# Sensor.net
KiCad netlist of a schematic drawn in Altium Designer
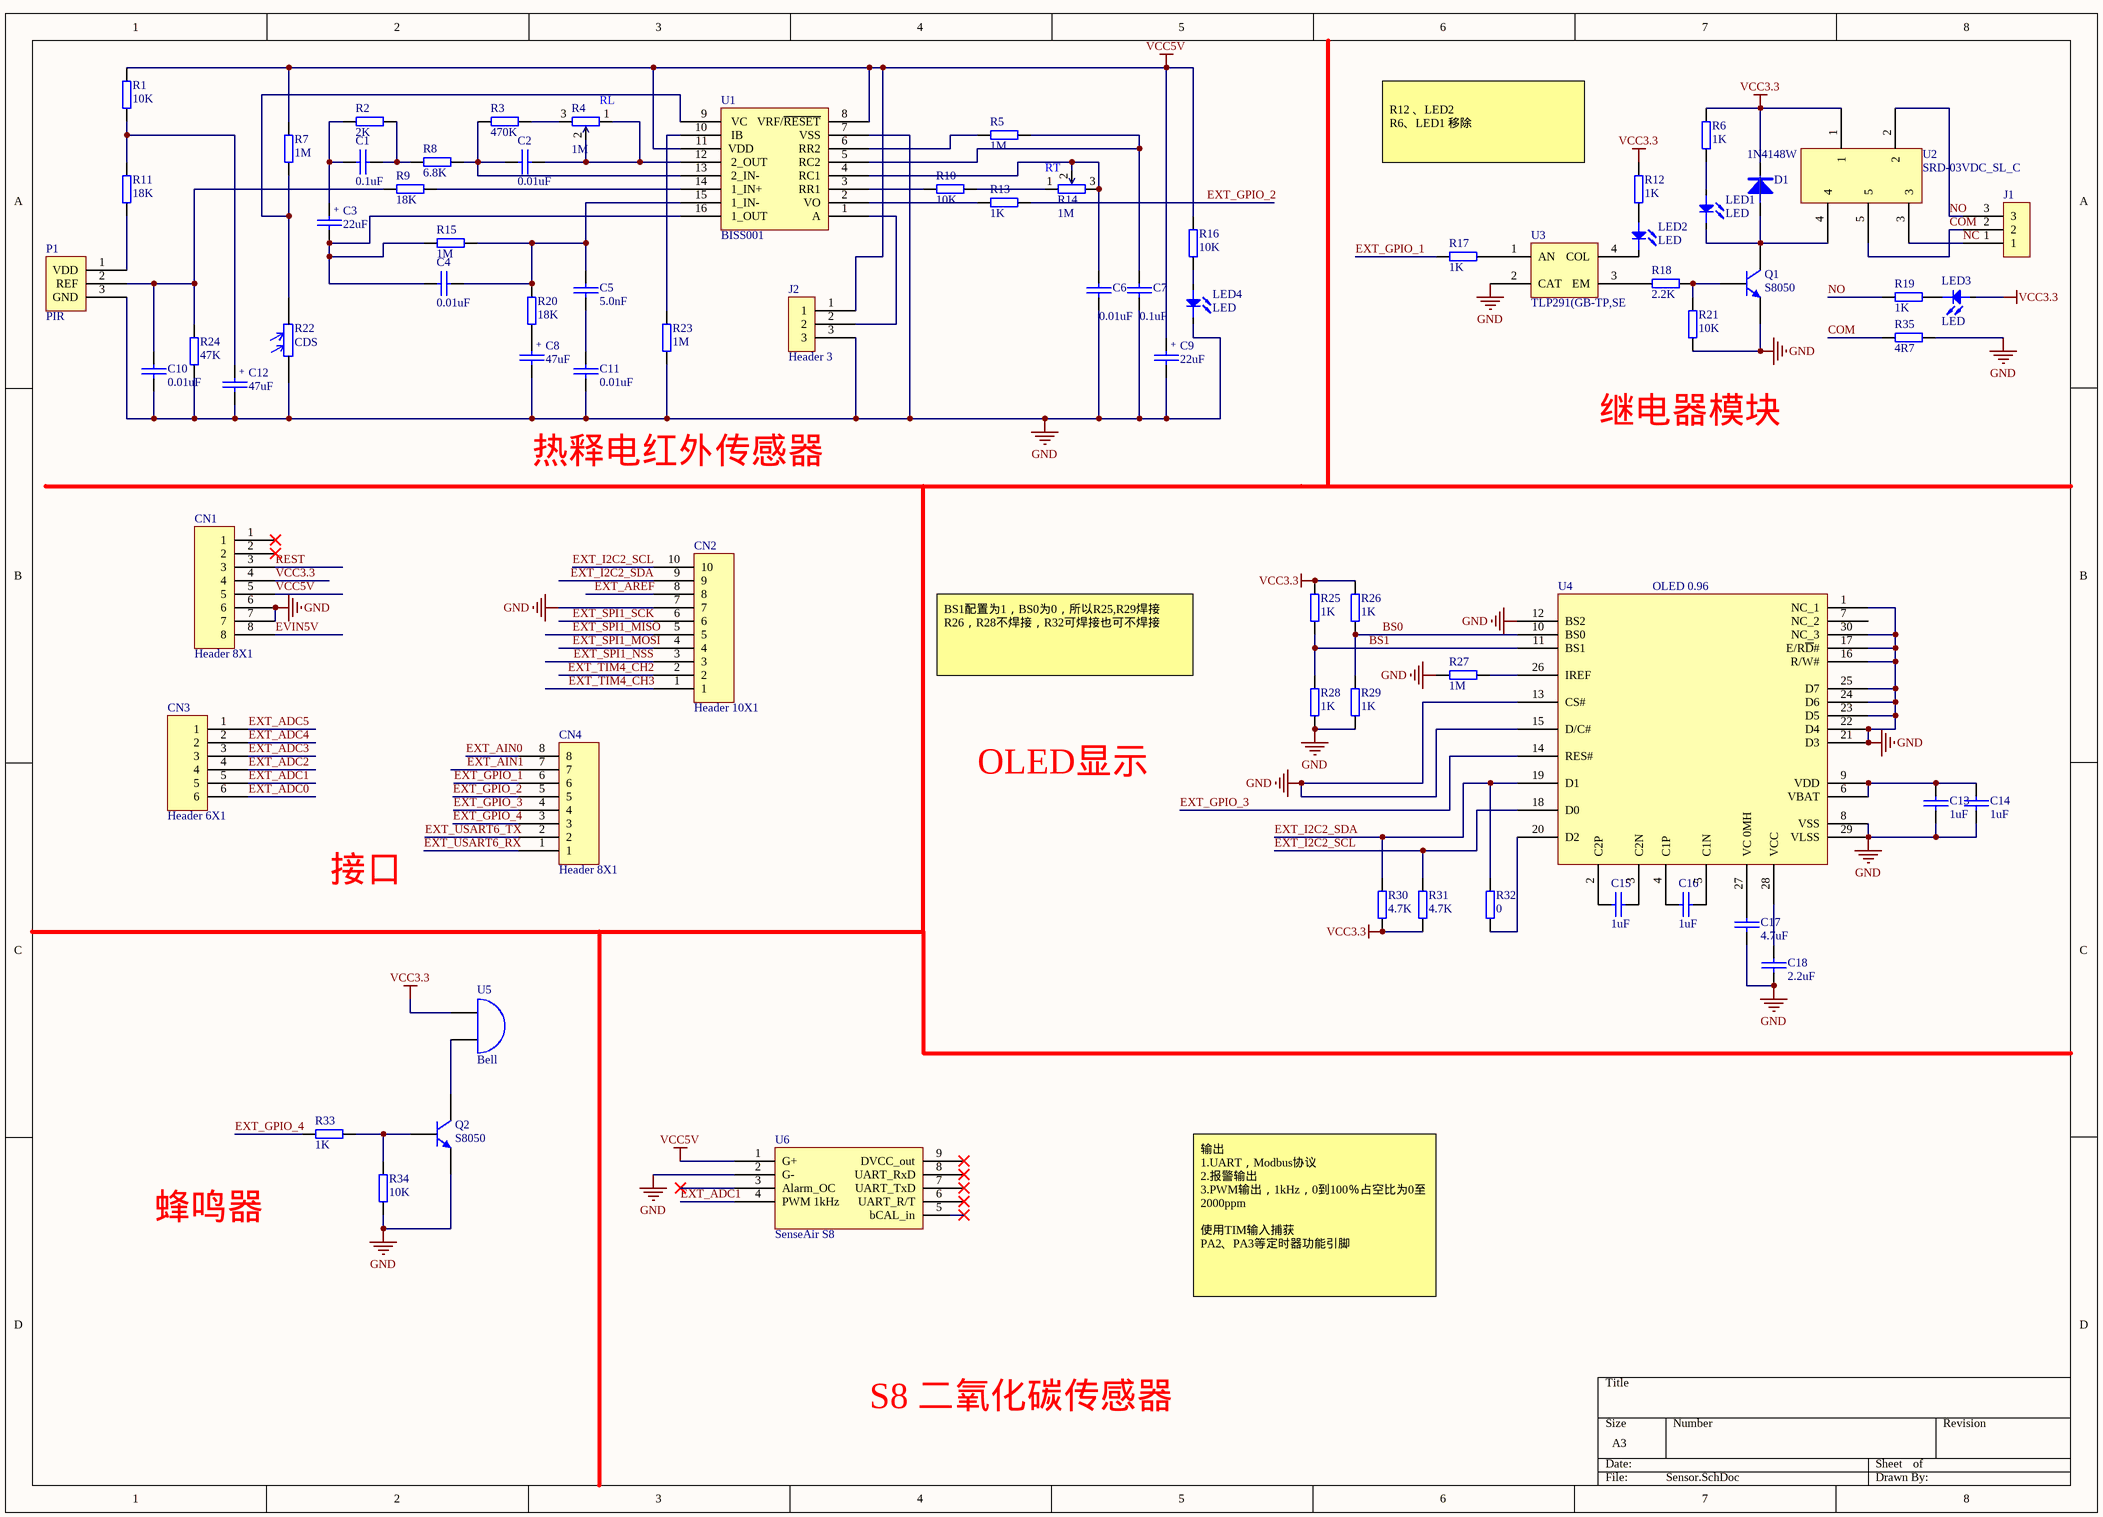
[diagram p0: Sensor.SchDoc]

(export (version "E")
  (design (tool "Eeschema 10.0.6"))
  (components
    (comp (ref "C1")
      (value "0.1uF")
      (footprint "0603 - CAP")
      (libsource (lib "practice") (part "Capacity_normal"))
    )
    (comp (ref "C2")
      (value "0.01uF")
      (footprint "0603 - CAP")
      (libsource (lib "practice") (part "Capacity_normal"))
    )
    (comp (ref "C3")
      (value "22uF")
      (footprint "C-钽贴A(S)_3216M_18(12)")
      (libsource (lib "practice") (part "Capacity_electric"))
    )
    (comp (ref "C4")
      (value "0.01uF")
      (footprint "0603 - CAP")
      (libsource (lib "practice") (part "Capacity_normal"))
    )
    (comp (ref "C5")
      (value "5.0nF")
      (footprint "0603 - CAP")
      (libsource (lib "practice") (part "Capacity_normal"))
    )
    (comp (ref "C6")
      (value "0.01uF")
      (footprint "0603 - CAP")
      (libsource (lib "practice") (part "Capacity_normal"))
    )
    (comp (ref "C7")
      (value "0.1uF")
      (footprint "0603 - CAP")
      (libsource (lib "practice") (part "Capacity_normal"))
    )
    (comp (ref "C8")
      (value "47uF")
      (footprint "C-钽贴A(S)_3216M_18(12)")
      (libsource (lib "practice") (part "Capacity_electric"))
    )
    (comp (ref "C9")
      (value "22uF")
      (footprint "C-钽贴A(S)_3216M_18(12)")
      (libsource (lib "practice") (part "Capacity_electric"))
    )
    (comp (ref "C10")
      (value "0.01uF")
      (footprint "0603 - CAP")
      (libsource (lib "practice") (part "Capacity_normal"))
    )
    (comp (ref "C11")
      (value "0.01uF")
      (footprint "0603 - CAP")
      (libsource (lib "practice") (part "Capacity_normal"))
    )
    (comp (ref "C12")
      (value "47uF")
      (footprint "C-钽贴A(S)_3216M_18(12)")
      (libsource (lib "practice") (part "Capacity_electric"))
    )
    (comp (ref "C13")
      (value "1uF")
      (footprint "0603 - CAP")
      (libsource (lib "practice") (part "Capacity_normal"))
    )
    (comp (ref "C14")
      (value "1uF")
      (footprint "0603 - CAP")
      (libsource (lib "practice") (part "Capacity_normal"))
    )
    (comp (ref "C15")
      (value "1uF")
      (footprint "0603 - CAP")
      (libsource (lib "practice") (part "Capacity_normal"))
    )
    (comp (ref "C16")
      (value "1uF")
      (footprint "0603 - CAP")
      (libsource (lib "practice") (part "Capacity_normal"))
    )
    (comp (ref "C17")
      (value "4.7uF")
      (footprint "0603 - CAP")
      (libsource (lib "practice") (part "Capacity_normal"))
    )
    (comp (ref "C18")
      (value "2.2uF")
      (footprint "0603 - CAP")
      (libsource (lib "practice") (part "Capacity_normal"))
    )
    (comp (ref "CN1") (value "Header 8X1") (footprint "HDR1X8") (libsource (lib "") (part "Header 8X1_1")))
    (comp (ref "CN2")
      (value "Header 10X1")
      (footprint "HDR1X10")
      (libsource (lib "practice") (part "Header 10X1"))
    )
    (comp (ref "CN3")
      (value "Header 6X1")
      (footprint "HDR1X6")
      (libsource (lib "practice") (part "Header 6X1"))
    )
    (comp (ref "CN4")
      (value "Header 8X1")
      (footprint "HDR1X8")
      (libsource (lib "practice") (part "Header 8X1"))
    )
    (comp (ref "D1") (value "1N4148W") (footprint "1N4148W") (libsource (lib "practice") (part "1N4148W")))
    (comp (ref "J1")
      (value "~")
      (footprint "HDR1X3 - duplicate1")
      (description "Header,3-pin")
      (libsource (lib "practice") (part "Header 3"))
    )
    (comp (ref "J2")
      (value "Header 3")
      (footprint "HDR1X3 - duplicate1")
      (description "Header,3-pin")
      (libsource (lib "") (part "Header 3_1"))
    )
    (comp (ref "LED1") (value "LED") (footprint "0603-LED") (libsource (lib "practice") (part "LED")))
    (comp (ref "LED2") (value "LED") (footprint "0603-LED") (libsource (lib "practice") (part "LED")))
    (comp (ref "LED3") (value "LED") (footprint "0603-LED") (libsource (lib "practice") (part "LED")))
    (comp (ref "LED4") (value "LED") (footprint "0603-LED") (libsource (lib "practice") (part "LED")))
    (comp (ref "P1") (value "PIR") (footprint "PIR") (libsource (lib "practice") (part "PIR")))
    (comp (ref "Q1") (value "S8050") (footprint "TO-92_3") (libsource (lib "practice") (part "S8050")))
    (comp (ref "Q2") (value "S8050") (footprint "TO-92_3") (libsource (lib "practice") (part "S8050")))
    (comp (ref "R1") (value "10K") (footprint "0603 - RES") (libsource (lib "practice") (part "RES")))
    (comp (ref "R2") (value "2K") (footprint "0603 - RES") (libsource (lib "practice") (part "RES")))
    (comp (ref "R3") (value "470K") (footprint "0603 - RES") (libsource (lib "practice") (part "RES")))
    (comp (ref "R4") (value "1M") (footprint "3296W") (libsource (lib "practice") (part "可调电阻")))
    (comp (ref "R5") (value "1M") (footprint "0603 - RES") (libsource (lib "practice") (part "RES")))
    (comp (ref "R6") (value "1K") (footprint "0603 - RES") (libsource (lib "practice") (part "RES")))
    (comp (ref "R7") (value "1M") (footprint "0603 - RES") (libsource (lib "practice") (part "RES")))
    (comp (ref "R8") (value "6.8K") (footprint "0603 - RES") (libsource (lib "practice") (part "RES")))
    (comp (ref "R9") (value "18K") (footprint "0603 - RES") (libsource (lib "practice") (part "RES")))
    (comp (ref "R10") (value "10K") (footprint "0603 - RES") (libsource (lib "practice") (part "RES")))
    (comp (ref "R11") (value "18K") (footprint "0603 - RES") (libsource (lib "practice") (part "RES")))
    (comp (ref "R12") (value "1K") (footprint "0603 - RES") (libsource (lib "practice") (part "RES")))
    (comp (ref "R13") (value "1K") (footprint "0603 - RES") (libsource (lib "practice") (part "RES")))
    (comp (ref "R14") (value "1M") (footprint "3296W") (libsource (lib "practice") (part "可调电阻")))
    (comp (ref "R15") (value "1M") (footprint "0603 - RES") (libsource (lib "practice") (part "RES")))
    (comp (ref "R16") (value "10K") (footprint "0603 - RES") (libsource (lib "practice") (part "RES")))
    (comp (ref "R17") (value "1K") (footprint "0603 - RES") (libsource (lib "practice") (part "RES")))
    (comp (ref "R18") (value "2.2K") (footprint "0603 - RES") (libsource (lib "practice") (part "RES")))
    (comp (ref "R19") (value "1K") (footprint "0603 - RES") (libsource (lib "practice") (part "RES")))
    (comp (ref "R20") (value "18K") (footprint "0603 - RES") (libsource (lib "practice") (part "RES")))
    (comp (ref "R21") (value "10K") (footprint "0603 - RES") (libsource (lib "practice") (part "RES")))
    (comp (ref "R22") (value "CDS") (footprint "RES-guangmin") (libsource (lib "practice") (part "光敏电阻")))
    (comp (ref "R23") (value "1M") (footprint "0603 - RES") (libsource (lib "practice") (part "RES")))
    (comp (ref "R24") (value "47K") (footprint "0603 - RES") (libsource (lib "practice") (part "RES")))
    (comp (ref "R25") (value "1K") (footprint "0603 - RES") (libsource (lib "practice") (part "RES")))
    (comp (ref "R26") (value "1K") (footprint "0603 - RES") (libsource (lib "practice") (part "RES")))
    (comp (ref "R27") (value "1M") (footprint "0603 - RES") (libsource (lib "practice") (part "RES")))
    (comp (ref "R28") (value "1K") (footprint "0603 - RES") (libsource (lib "practice") (part "RES")))
    (comp (ref "R29") (value "1K") (footprint "0603 - RES") (libsource (lib "practice") (part "RES")))
    (comp (ref "R30") (value "4.7K") (footprint "0603 - RES") (libsource (lib "practice") (part "RES")))
    (comp (ref "R31") (value "4.7K") (footprint "0603 - RES") (libsource (lib "practice") (part "RES")))
    (comp (ref "R32") (value "0") (footprint "0603 - RES") (libsource (lib "电阻") (part "RES")))
    (comp (ref "R33") (value "1K") (footprint "0603 - RES") (libsource (lib "practice") (part "RES")))
    (comp (ref "R34") (value "10K") (footprint "0603 - RES") (libsource (lib "practice") (part "RES")))
    (comp (ref "R35") (value "4R7") (footprint "0603 - RES") (libsource (lib "practice") (part "RES")))
    (comp (ref "U1")
      (value "BISS001")
      (footprint "SOP-16_150mil")
      (description "热释电传感器")
      (libsource (lib "practice") (part "BISS001"))
    )
    (comp (ref "U2")
      (value "SRD-03VDC_SL_C")
      (footprint "SRD-03VDC-SL-C")
      (description "SL，3V 继电器模块")
      (libsource (lib "practice") (part "SRD-03VDC_SL_C"))
    )
    (comp (ref "U3")
      (value "TLP291(GB-TP,SE")
      (footprint "TLP291(GB-TP,SE")
      (libsource (lib "practice") (part "TLP291(GB-TP,SE"))
    )
    (comp (ref "U4")
      (value "OLED 0.96")
      (footprint "oled 0.96")
      (description "中景园 0.96寸OLED 30pin")
      (libsource (lib "practice") (part "OLED 0.96"))
    )
    (comp (ref "U5") (value "Bell") (footprint "BUZZER_mini") (libsource (lib "practice") (part "Bell")))
    (comp (ref "U6")
      (value "SenseAir S8")
      (footprint "SenseAir S8")
      (libsource (lib "practice") (part "SenseAir S8"))
    )
  )
  (nets
    (net (code "1") (name "/BS0") (class "Default")
      (node (ref "R26") (pin "1") (pinfunction "1_1") (pintype "passive"))
      (node (ref "R29") (pin "2") (pinfunction "2_2") (pintype "passive"))
      (node (ref "U4") (pin "10") (pinfunction "BS0_10") (pintype "passive"))
    )
    (net (code "2") (name "/BS1") (class "Default")
      (node (ref "R25") (pin "1") (pinfunction "1_1") (pintype "passive"))
      (node (ref "R28") (pin "2") (pinfunction "2_2") (pintype "passive"))
      (node (ref "U4") (pin "11") (pinfunction "BS1_11") (pintype "passive"))
    )
    (net (code "3") (name "/COM") (class "Default")
      (node (ref "J1") (pin "2") (pinfunction "2_2") (pintype "passive"))
      (node (ref "R35") (pin "1") (pinfunction "1_1") (pintype "passive"))
      (node (ref "U2") (pin "5") (pinfunction "5_5") (pintype "passive"))
    )
    (net (code "4") (name "/EVIN5V") (class "Default")
      (node (ref "CN1") (pin "8") (pinfunction "8_8") (pintype "passive"))
    )
    (net (code "5") (name "/EXT_ADC0") (class "Default")
      (node (ref "CN3") (pin "6") (pinfunction "6_6") (pintype "passive"))
    )
    (net (code "6") (name "/EXT_ADC1") (class "Default")
      (node (ref "CN3") (pin "5") (pinfunction "5_5") (pintype "passive"))
      (node (ref "U6") (pin "4") (pinfunction "PWM_1kHz_4") (pintype "passive"))
    )
    (net (code "7") (name "/EXT_ADC2") (class "Default")
      (node (ref "CN3") (pin "4") (pinfunction "4_4") (pintype "passive"))
    )
    (net (code "8") (name "/EXT_ADC3") (class "Default")
      (node (ref "CN3") (pin "3") (pinfunction "3_3") (pintype "passive"))
    )
    (net (code "9") (name "/EXT_ADC4") (class "Default")
      (node (ref "CN3") (pin "2") (pinfunction "2_2") (pintype "passive"))
    )
    (net (code "10") (name "/EXT_ADC5") (class "Default")
      (node (ref "CN3") (pin "1") (pinfunction "1_1") (pintype "passive"))
    )
    (net (code "11") (name "/EXT_AIN0") (class "Default")
      (node (ref "CN4") (pin "8") (pinfunction "8_8") (pintype "passive"))
    )
    (net (code "12") (name "/EXT_AIN1") (class "Default")
      (node (ref "CN4") (pin "7") (pinfunction "7_7") (pintype "passive"))
    )
    (net (code "13") (name "/EXT_AREF") (class "Default")
      (node (ref "CN2") (pin "8") (pinfunction "8_8") (pintype "passive"))
    )
    (net (code "14") (name "/EXT_GPIO_1") (class "Default")
      (node (ref "CN4") (pin "6") (pinfunction "6_6") (pintype "passive"))
      (node (ref "R17") (pin "1") (pinfunction "1_1") (pintype "passive"))
    )
    (net (code "15") (name "/EXT_GPIO_2") (class "Default")
      (node (ref "CN4") (pin "5") (pinfunction "5_5") (pintype "passive"))
      (node (ref "R13") (pin "2") (pinfunction "2_2") (pintype "passive"))
    )
    (net (code "16") (name "/EXT_GPIO_3") (class "Default")
      (node (ref "CN4") (pin "4") (pinfunction "4_4") (pintype "passive"))
      (node (ref "U4") (pin "14") (pinfunction "RES#_14") (pintype "passive"))
    )
    (net (code "17") (name "/EXT_GPIO_4") (class "Default")
      (node (ref "CN4") (pin "3") (pinfunction "3_3") (pintype "passive"))
      (node (ref "R33") (pin "1") (pinfunction "1_1") (pintype "passive"))
    )
    (net (code "18") (name "/EXT_I2C2_SCL") (class "Default")
      (node (ref "CN2") (pin "10") (pinfunction "10_10") (pintype "passive"))
      (node (ref "R31") (pin "2") (pinfunction "2_2") (pintype "passive"))
      (node (ref "U4") (pin "18") (pinfunction "D0_18") (pintype "passive"))
    )
    (net (code "19") (name "/EXT_I2C2_SDA") (class "Default")
      (node (ref "CN2") (pin "9") (pinfunction "9_9") (pintype "passive"))
      (node (ref "R30") (pin "2") (pinfunction "2_2") (pintype "passive"))
      (node (ref "R32") (pin "2") (pinfunction "2_2") (pintype "passive"))
      (node (ref "U4") (pin "19") (pinfunction "D1_19") (pintype "passive"))
    )
    (net (code "20") (name "/EXT_SPI1_MISO") (class "Default")
      (node (ref "CN2") (pin "5") (pinfunction "5_5") (pintype "passive"))
    )
    (net (code "21") (name "/EXT_SPI1_MOSI") (class "Default")
      (node (ref "CN2") (pin "4") (pinfunction "4_4") (pintype "passive"))
    )
    (net (code "22") (name "/EXT_SPI1_NSS") (class "Default")
      (node (ref "CN2") (pin "3") (pinfunction "3_3") (pintype "passive"))
    )
    (net (code "23") (name "/EXT_SPI1_SCK") (class "Default")
      (node (ref "CN2") (pin "6") (pinfunction "6_6") (pintype "passive"))
    )
    (net (code "24") (name "/EXT_TIM4_CH2") (class "Default")
      (node (ref "CN2") (pin "2") (pinfunction "2_2") (pintype "passive"))
    )
    (net (code "25") (name "/EXT_TIM4_CH3") (class "Default")
      (node (ref "CN2") (pin "1") (pinfunction "1_1") (pintype "passive"))
    )
    (net (code "26") (name "/EXT_USART6_RX") (class "Default")
      (node (ref "CN4") (pin "1") (pinfunction "1_1") (pintype "passive"))
    )
    (net (code "27") (name "/EXT_USART6_TX") (class "Default")
      (node (ref "CN4") (pin "2") (pinfunction "2_2") (pintype "passive"))
    )
    (net (code "28") (name "/NC") (class "Default")
      (node (ref "J1") (pin "1") (pinfunction "1_1") (pintype "passive"))
      (node (ref "U2") (pin "3") (pinfunction "3_3") (pintype "passive"))
    )
    (net (code "29") (name "/NO") (class "Default")
      (node (ref "J1") (pin "3") (pinfunction "3_3") (pintype "passive"))
      (node (ref "R19") (pin "1") (pinfunction "1_1") (pintype "passive"))
      (node (ref "U2") (pin "2") (pinfunction "2_2") (pintype "passive"))
    )
    (net (code "30") (name "/REST") (class "Default")
      (node (ref "CN1") (pin "3") (pinfunction "3_3") (pintype "passive"))
    )
    (net (code "31") (name "GND") (class "Default")
      (node (ref "C10") (pin "2") (pinfunction "2_2") (pintype "passive"))
      (node (ref "C11") (pin "2") (pinfunction "2_2") (pintype "passive"))
      (node (ref "C12") (pin "2") (pinfunction "2_2") (pintype "passive"))
      (node (ref "C13") (pin "1") (pinfunction "1_1") (pintype "passive"))
      (node (ref "C14") (pin "1") (pinfunction "1_1") (pintype "passive"))
      (node (ref "C17") (pin "1") (pinfunction "1_1") (pintype "passive"))
      (node (ref "C18") (pin "1") (pinfunction "1_1") (pintype "passive"))
      (node (ref "C6") (pin "2") (pinfunction "2_2") (pintype "passive"))
      (node (ref "C7") (pin "2") (pinfunction "2_2") (pintype "passive"))
      (node (ref "C8") (pin "2") (pinfunction "2_2") (pintype "passive"))
      (node (ref "C9") (pin "2") (pinfunction "2_2") (pintype "passive"))
      (node (ref "CN1") (pin "6") (pinfunction "6_6") (pintype "passive"))
      (node (ref "CN1") (pin "7") (pinfunction "7_7") (pintype "passive"))
      (node (ref "CN2") (pin "7") (pinfunction "7_7") (pintype "passive"))
      (node (ref "J2") (pin "3") (pinfunction "3_3") (pintype "passive"))
      (node (ref "LED4") (pin "2") (pintype "passive"))
      (node (ref "P1") (pin "3") (pinfunction "GND_3") (pintype "passive"))
      (node (ref "Q1") (pin "1") (pinfunction "E_1") (pintype "passive"))
      (node (ref "Q2") (pin "1") (pinfunction "E_1") (pintype "passive"))
      (node (ref "R21") (pin "2") (pinfunction "2_2") (pintype "passive"))
      (node (ref "R22") (pin "1") (pinfunction "1_1") (pintype "passive"))
      (node (ref "R23") (pin "1") (pinfunction "1_1") (pintype "passive"))
      (node (ref "R24") (pin "1") (pinfunction "1_1") (pintype "passive"))
      (node (ref "R27") (pin "2") (pinfunction "2_2") (pintype "passive"))
      (node (ref "R28") (pin "1") (pinfunction "1_1") (pintype "passive"))
      (node (ref "R29") (pin "1") (pinfunction "1_1") (pintype "passive"))
      (node (ref "R34") (pin "1") (pinfunction "1_1") (pintype "passive"))
      (node (ref "R35") (pin "2") (pinfunction "2_2") (pintype "passive"))
      (node (ref "U1") (pin "7") (pinfunction "VSS_7") (pintype "passive"))
      (node (ref "U3") (pin "2") (pinfunction "CAT_2") (pintype "passive"))
      (node (ref "U4") (pin "1") (pinfunction "NC_1_1") (pintype "passive"))
      (node (ref "U4") (pin "12") (pinfunction "BS2_12") (pintype "passive"))
      (node (ref "U4") (pin "13") (pinfunction "CS#_13") (pintype "passive"))
      (node (ref "U4") (pin "15") (pinfunction "D/C#_15") (pintype "passive"))
      (node (ref "U4") (pin "16") (pinfunction "R/W#_16") (pintype "passive"))
      (node (ref "U4") (pin "17") (pinfunction "E/R~{D}#_17") (pintype "passive"))
      (node (ref "U4") (pin "21") (pinfunction "D3_21") (pintype "passive"))
      (node (ref "U4") (pin "22") (pinfunction "D4_22") (pintype "passive"))
      (node (ref "U4") (pin "23") (pinfunction "D5_23") (pintype "passive"))
      (node (ref "U4") (pin "24") (pinfunction "D6_24") (pintype "passive"))
      (node (ref "U4") (pin "25") (pinfunction "D7_25") (pintype "passive"))
      (node (ref "U4") (pin "29") (pinfunction "VLSS_29") (pintype "passive"))
      (node (ref "U4") (pin "30") (pinfunction "NC_3_30") (pintype "passive"))
      (node (ref "U4") (pin "8") (pinfunction "VSS_8") (pintype "passive"))
      (node (ref "U6") (pin "2") (pinfunction "G-_2") (pintype "passive"))
    )
    (net (code "32") (name "Net-(C1-Pad1)") (class "Default")
      (node (ref "C1") (pin "1") (pinfunction "1_1") (pintype "passive"))
      (node (ref "R2") (pin "2") (pinfunction "2_2") (pintype "passive"))
      (node (ref "R8") (pin "1") (pinfunction "1_1") (pintype "passive"))
    )
    (net (code "33") (name "Net-(C1-Pad2)") (class "Default")
      (node (ref "C1") (pin "2") (pinfunction "2_2") (pintype "passive"))
      (node (ref "C3") (pin "1") (pinfunction "1_1") (pintype "passive"))
      (node (ref "R2") (pin "1") (pinfunction "1_1") (pintype "passive"))
    )
    (net (code "34") (name "Net-(C8-Pad1)") (class "Default")
      (node (ref "C8") (pin "1") (pinfunction "1_1") (pintype "passive"))
      (node (ref "R20") (pin "1") (pinfunction "1_1") (pintype "passive"))
    )
    (net (code "35") (name "Net-(C11-Pad1)") (class "Default")
      (node (ref "C11") (pin "1") (pinfunction "1_1") (pintype "passive"))
      (node (ref "C5") (pin "2") (pinfunction "2_2") (pintype "passive"))
    )
    (net (code "36") (name "Net-(C12-Pad1)") (class "Default")
      (node (ref "C12") (pin "1") (pinfunction "1_1") (pintype "passive"))
      (node (ref "R1") (pin "1") (pinfunction "1_1") (pintype "passive"))
      (node (ref "R11") (pin "2") (pinfunction "2_2") (pintype "passive"))
    )
    (net (code "37") (name "Net-(D1-A)") (class "Default")
      (node (ref "D1") (pin "1") (pinfunction "A_1") (pintype "passive"))
      (node (ref "LED1") (pin "2") (pintype "passive"))
      (node (ref "Q1") (pin "3") (pinfunction "C_3") (pintype "passive"))
      (node (ref "U2") (pin "4") (pinfunction "4_4") (pintype "passive"))
    )
    (net (code "38") (name "Net-(LED1-Pad1)") (class "Default")
      (node (ref "LED1") (pin "1") (pintype "passive"))
      (node (ref "R6") (pin "1") (pinfunction "1_1") (pintype "passive"))
    )
    (net (code "39") (name "Net-(LED2-Pad1)") (class "Default")
      (node (ref "LED2") (pin "1") (pintype "passive"))
      (node (ref "R12") (pin "1") (pinfunction "1_1") (pintype "passive"))
    )
    (net (code "40") (name "Net-(LED3-Pad2)") (class "Default")
      (node (ref "LED3") (pin "2") (pintype "passive"))
      (node (ref "R19") (pin "2") (pinfunction "2_2") (pintype "passive"))
    )
    (net (code "41") (name "Net-(LED4-Pad1)") (class "Default")
      (node (ref "LED4") (pin "1") (pintype "passive"))
      (node (ref "R16") (pin "1") (pinfunction "1_1") (pintype "passive"))
    )
    (net (code "42") (name "Net-(P1-REF)") (class "Default")
      (node (ref "C10") (pin "1") (pinfunction "1_1") (pintype "passive"))
      (node (ref "P1") (pin "2") (pinfunction "REF_2") (pintype "passive"))
      (node (ref "R24") (pin "2") (pinfunction "2_2") (pintype "passive"))
      (node (ref "R9") (pin "2") (pinfunction "2_2") (pintype "passive"))
    )
    (net (code "43") (name "Net-(P1-VDD)") (class "Default")
      (node (ref "P1") (pin "1") (pinfunction "VDD_1") (pintype "passive"))
      (node (ref "R11") (pin "1") (pinfunction "1_1") (pintype "passive"))
    )
    (net (code "44") (name "Net-(Q1-B)") (class "Default")
      (node (ref "Q1") (pin "2") (pinfunction "B_2") (pintype "passive"))
      (node (ref "R18") (pin "1") (pinfunction "1_1") (pintype "passive"))
      (node (ref "R21") (pin "1") (pinfunction "1_1") (pintype "passive"))
    )
    (net (code "45") (name "Net-(Q2-B)") (class "Default")
      (node (ref "Q2") (pin "2") (pinfunction "B_2") (pintype "passive"))
      (node (ref "R33") (pin "2") (pinfunction "2_2") (pintype "passive"))
      (node (ref "R34") (pin "2") (pinfunction "2_2") (pintype "passive"))
    )
    (net (code "46") (name "Net-(Q2-C)") (class "Default")
      (node (ref "Q2") (pin "3") (pinfunction "C_3") (pintype "passive"))
      (node (ref "U5") (pin "2") (pinfunction "B_2") (pintype "passive"))
    )
    (net (code "47") (name "Net-(R3-Pad2)") (class "Default")
      (node (ref "R3") (pin "2") (pinfunction "2_2") (pintype "passive"))
      (node (ref "R4") (pin "3") (pinfunction "3_3") (pintype "passive"))
    )
    (net (code "48") (name "Net-(R10-Pad1)") (class "Default")
      (node (ref "R10") (pin "1") (pinfunction "1_1") (pintype "passive"))
      (node (ref "R14") (pin "1") (pinfunction "1_1") (pintype "passive"))
    )
    (net (code "49") (name "Net-(U1-A)") (class "Default")
      (node (ref "J2") (pin "2") (pinfunction "2_2") (pintype "passive"))
      (node (ref "U1") (pin "1") (pinfunction "A_1") (pintype "passive"))
    )
    (net (code "50") (name "Net-(U1-RC1)") (class "Default")
      (node (ref "C6") (pin "1") (pinfunction "1_1") (pintype "passive"))
      (node (ref "R14") (pin "2") (pinfunction "2_2") (pintype "passive"))
      (node (ref "R14") (pin "3") (pinfunction "3_3") (pintype "passive"))
      (node (ref "U1") (pin "4") (pinfunction "RC1_4") (pintype "passive"))
    )
    (net (code "51") (name "Net-(U1-RC2)") (class "Default")
      (node (ref "C7") (pin "1") (pinfunction "1_1") (pintype "passive"))
      (node (ref "R5") (pin "1") (pinfunction "1_1") (pintype "passive"))
      (node (ref "U1") (pin "5") (pinfunction "RC2_5") (pintype "passive"))
    )
    (net (code "52") (name "Net-(U1-RR1)") (class "Default")
      (node (ref "R10") (pin "2") (pinfunction "2_2") (pintype "passive"))
      (node (ref "U1") (pin "3") (pinfunction "RR1_3") (pintype "passive"))
    )
    (net (code "53") (name "Net-(U1-VO)") (class "Default")
      (node (ref "R13") (pin "1") (pinfunction "1_1") (pintype "passive"))
      (node (ref "U1") (pin "2") (pinfunction "VO_2") (pintype "passive"))
    )
    (net (code "54") (name "Net-(U1-_1_IN+)") (class "Default")
      (node (ref "R9") (pin "1") (pinfunction "1_1") (pintype "passive"))
      (node (ref "U1") (pin "14") (pinfunction "_1_IN+_14") (pintype "passive"))
    )
    (net (code "55") (name "Net-(U1-_1_IN-)") (class "Default")
      (node (ref "C4") (pin "2") (pinfunction "2_2") (pintype "passive"))
      (node (ref "C5") (pin "1") (pinfunction "1_1") (pintype "passive"))
      (node (ref "R15") (pin "1") (pinfunction "1_1") (pintype "passive"))
      (node (ref "R20") (pin "2") (pinfunction "2_2") (pintype "passive"))
      (node (ref "U1") (pin "15") (pinfunction "_1_IN-_15") (pintype "passive"))
    )
    (net (code "56") (name "Net-(U1-_1_OUT)") (class "Default")
      (node (ref "C3") (pin "2") (pinfunction "2_2") (pintype "passive"))
      (node (ref "C4") (pin "1") (pinfunction "1_1") (pintype "passive"))
      (node (ref "R15") (pin "2") (pinfunction "2_2") (pintype "passive"))
      (node (ref "U1") (pin "16") (pinfunction "_1_OUT_16") (pintype "passive"))
    )
    (net (code "57") (name "Net-(U1-_2_IN-)") (class "Default")
      (node (ref "C2") (pin "1") (pinfunction "1_1") (pintype "passive"))
      (node (ref "R3") (pin "1") (pinfunction "1_1") (pintype "passive"))
      (node (ref "R8") (pin "2") (pinfunction "2_2") (pintype "passive"))
      (node (ref "U1") (pin "13") (pinfunction "_2_IN-_13") (pintype "passive"))
    )
    (net (code "58") (name "Net-(U1-_2_OUT)") (class "Default")
      (node (ref "C2") (pin "2") (pinfunction "2_2") (pintype "passive"))
      (node (ref "R4") (pin "1") (pinfunction "1_1") (pintype "passive"))
      (node (ref "R4") (pin "2") (pinfunction "2_2") (pintype "passive"))
      (node (ref "U1") (pin "12") (pinfunction "_2_OUT_12") (pintype "passive"))
    )
    (net (code "59") (name "Net-(U1-_IB)") (class "Default")
      (node (ref "R23") (pin "2") (pinfunction "2_2") (pintype "passive"))
      (node (ref "U1") (pin "10") (pinfunction "_IB_10") (pintype "passive"))
    )
    (net (code "60") (name "Net-(U1-_RR2)") (class "Default")
      (node (ref "R5") (pin "2") (pinfunction "2_2") (pintype "passive"))
      (node (ref "U1") (pin "6") (pinfunction "_RR2_6") (pintype "passive"))
    )
    (net (code "61") (name "Net-(U1-_VC)") (class "Default")
      (node (ref "R22") (pin "2") (pinfunction "2_2") (pintype "passive"))
      (node (ref "R7") (pin "1") (pinfunction "1_1") (pintype "passive"))
      (node (ref "U1") (pin "9") (pinfunction "_VC_9") (pintype "passive"))
    )
    (net (code "62") (name "Net-(U3-AN)") (class "Default")
      (node (ref "R17") (pin "2") (pinfunction "2_2") (pintype "passive"))
      (node (ref "U3") (pin "1") (pinfunction "AN_1") (pintype "passive"))
    )
    (net (code "63") (name "Net-(U3-COL)") (class "Default")
      (node (ref "LED2") (pin "2") (pintype "passive"))
      (node (ref "U3") (pin "4") (pinfunction "COL_4") (pintype "passive"))
    )
    (net (code "64") (name "Net-(U3-EM)") (class "Default")
      (node (ref "R18") (pin "2") (pinfunction "2_2") (pintype "passive"))
      (node (ref "U3") (pin "3") (pinfunction "EM_3") (pintype "passive"))
    )
    (net (code "65") (name "Net-(U4-C1N)") (class "Default")
      (node (ref "C16") (pin "1") (pinfunction "1_1") (pintype "passive"))
      (node (ref "U4") (pin "5") (pinfunction "C1N_5") (pintype "passive"))
    )
    (net (code "66") (name "Net-(U4-C1P)") (class "Default")
      (node (ref "C16") (pin "2") (pinfunction "2_2") (pintype "passive"))
      (node (ref "U4") (pin "4") (pinfunction "C1P_4") (pintype "passive"))
    )
    (net (code "67") (name "Net-(U4-C2N)") (class "Default")
      (node (ref "C15") (pin "1") (pinfunction "1_1") (pintype "passive"))
      (node (ref "U4") (pin "3") (pinfunction "C2N_3") (pintype "passive"))
    )
    (net (code "68") (name "Net-(U4-C2P)") (class "Default")
      (node (ref "C15") (pin "2") (pinfunction "2_2") (pintype "passive"))
      (node (ref "U4") (pin "2") (pinfunction "C2P_2") (pintype "passive"))
    )
    (net (code "69") (name "Net-(U4-D2)") (class "Default")
      (node (ref "R32") (pin "1") (pinfunction "1_1") (pintype "passive"))
      (node (ref "U4") (pin "20") (pinfunction "D2_20") (pintype "passive"))
    )
    (net (code "70") (name "Net-(U4-IREF)") (class "Default")
      (node (ref "R27") (pin "1") (pinfunction "1_1") (pintype "passive"))
      (node (ref "U4") (pin "26") (pinfunction "IREF_26") (pintype "passive"))
    )
    (net (code "71") (name "Net-(U4-VBAT)") (class "Default")
      (node (ref "C13") (pin "2") (pinfunction "2_2") (pintype "passive"))
      (node (ref "C14") (pin "2") (pinfunction "2_2") (pintype "passive"))
      (node (ref "U4") (pin "6") (pinfunction "VBAT_6") (pintype "passive"))
      (node (ref "U4") (pin "9") (pinfunction "VDD_9") (pintype "passive"))
    )
    (net (code "72") (name "Net-(U4-VCC)") (class "Default")
      (node (ref "C18") (pin "2") (pinfunction "2_2") (pintype "passive"))
      (node (ref "U4") (pin "28") (pinfunction "VCC_28") (pintype "passive"))
    )
    (net (code "73") (name "Net-(U4-VC_0MH)") (class "Default")
      (node (ref "C17") (pin "2") (pinfunction "2_2") (pintype "passive"))
      (node (ref "U4") (pin "27") (pinfunction "VC_0MH_27") (pintype "passive"))
    )
    (net (code "74") (name "VCC3.3") (class "Default")
      (node (ref "CN1") (pin "4") (pinfunction "4_4") (pintype "passive"))
      (node (ref "D1") (pin "2") (pinfunction "K_2") (pintype "passive"))
      (node (ref "LED3") (pin "1") (pintype "passive"))
      (node (ref "R12") (pin "2") (pinfunction "2_2") (pintype "passive"))
      (node (ref "R25") (pin "2") (pinfunction "2_2") (pintype "passive"))
      (node (ref "R26") (pin "2") (pinfunction "2_2") (pintype "passive"))
      (node (ref "R30") (pin "1") (pinfunction "1_1") (pintype "passive"))
      (node (ref "R31") (pin "1") (pinfunction "1_1") (pintype "passive"))
      (node (ref "R6") (pin "2") (pinfunction "2_2") (pintype "passive"))
      (node (ref "U2") (pin "1") (pinfunction "1_1") (pintype "passive"))
      (node (ref "U5") (pin "1") (pinfunction "A_1") (pintype "passive"))
    )
    (net (code "75") (name "VCC5V") (class "Default")
      (node (ref "C9") (pin "1") (pinfunction "1_1") (pintype "passive"))
      (node (ref "CN1") (pin "5") (pinfunction "5_5") (pintype "passive"))
      (node (ref "J2") (pin "1") (pinfunction "1_1") (pintype "passive"))
      (node (ref "R1") (pin "2") (pinfunction "2_2") (pintype "passive"))
      (node (ref "R16") (pin "2") (pinfunction "2_2") (pintype "passive"))
      (node (ref "R7") (pin "2") (pinfunction "2_2") (pintype "passive"))
      (node (ref "U1") (pin "11") (pinfunction "VDD_11") (pintype "passive"))
      (node (ref "U1") (pin "8") (pinfunction "_VRF/~{RESET}_8") (pintype "passive"))
      (node (ref "U6") (pin "1") (pinfunction "G+_1") (pintype "passive"))
    )
    (net (code "76") (name "unconnected-(CN1-Pad1)") (class "Default")
      (node (ref "CN1") (pin "1") (pinfunction "1_1") (pintype "passive+no_connect"))
    )
    (net (code "77") (name "unconnected-(CN1-Pad2)") (class "Default")
      (node (ref "CN1") (pin "2") (pinfunction "2_2") (pintype "passive+no_connect"))
    )
    (net (code "78") (name "unconnected-(U4-NC_2-Pad7)") (class "Default")
      (node (ref "U4") (pin "7") (pinfunction "NC_2_7") (pintype "passive"))
    )
    (net (code "79") (name "unconnected-(U6-Alarm_OC-Pad3)") (class "Default")
      (node (ref "U6") (pin "3") (pinfunction "Alarm_OC_3") (pintype "passive+no_connect"))
    )
    (net (code "80") (name "unconnected-(U6-DVCC_out-Pad9)") (class "Default")
      (node (ref "U6") (pin "9") (pinfunction "DVCC_out_9") (pintype "passive+no_connect"))
    )
    (net (code "81") (name "unconnected-(U6-UART_RxD-Pad8)") (class "Default")
      (node (ref "U6") (pin "8") (pinfunction "UART_RxD_8") (pintype "passive+no_connect"))
    )
    (net (code "82") (name "unconnected-(U6-UART_R{slash}T-Pad6)") (class "Default")
      (node (ref "U6") (pin "6") (pinfunction "UART_R/T_6") (pintype "passive+no_connect"))
    )
    (net (code "83") (name "unconnected-(U6-UART_TxD-Pad7)") (class "Default")
      (node (ref "U6") (pin "7") (pinfunction "UART_TxD_7") (pintype "passive+no_connect"))
    )
    (net (code "84") (name "unconnected-(U6-bCAL_in-Pad5)") (class "Default")
      (node (ref "U6") (pin "5") (pinfunction "bCAL_in_5") (pintype "passive+no_connect"))
    )
  )
)
